# l6727a-5v.net
KiCad netlist of a schematic drawn in EAGLE
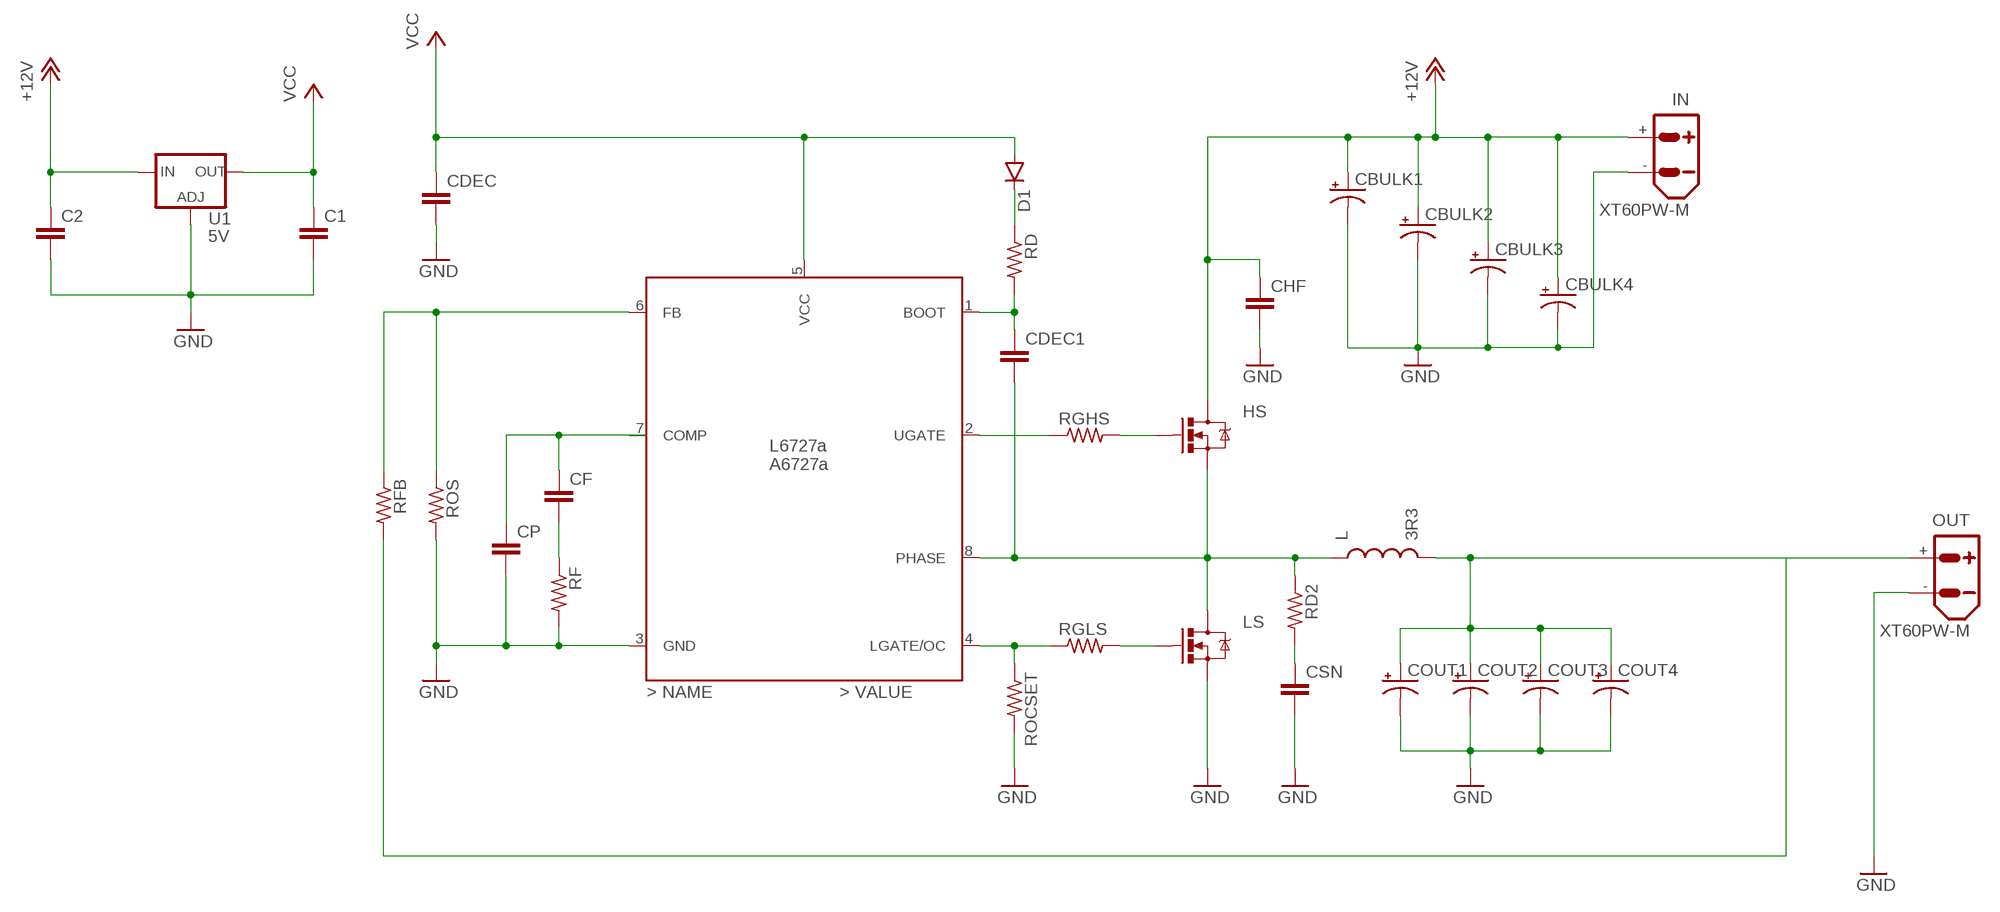
[diagram p0: schematic, sheet 1]

(export (version "E")
  (design (tool "Eeschema 10.0.6"))
  (components
    (comp (ref "C1")
      (value "C-EUC1206")
      (footprint "eagle-import:C1206")
      (libsource (lib "eagle-import") (part "C-EUC1206"))
    )
    (comp (ref "C2")
      (value "C-EUC1206")
      (footprint "eagle-import:C1206")
      (libsource (lib "eagle-import") (part "C-EUC1206"))
    )
    (comp (ref "CBULK1")
      (value "CPOL-USSANYO_SMD_E7")
      (footprint "eagle-import:SANYO-OSCON_SMD_E7")
      (libsource (lib "eagle-import") (part "CPOL-USSANYO_SMD_E7"))
    )
    (comp (ref "CBULK2")
      (value "CPOL-USSANYO_SMD_E7")
      (footprint "eagle-import:SANYO-OSCON_SMD_E7")
      (libsource (lib "eagle-import") (part "CPOL-USSANYO_SMD_E7"))
    )
    (comp (ref "CBULK3")
      (value "CPOL-USSANYO_SMD_E7")
      (footprint "eagle-import:SANYO-OSCON_SMD_E7")
      (libsource (lib "eagle-import") (part "CPOL-USSANYO_SMD_E7"))
    )
    (comp (ref "CBULK4")
      (value "CPOL-USSANYO_SMD_E7")
      (footprint "eagle-import:SANYO-OSCON_SMD_E7")
      (libsource (lib "eagle-import") (part "CPOL-USSANYO_SMD_E7"))
    )
    (comp (ref "CDEC")
      (value "C-EUC1206")
      (footprint "eagle-import:C1206")
      (libsource (lib "eagle-import") (part "C-EUC1206"))
    )
    (comp (ref "CDEC1")
      (value "C-EUC1206")
      (footprint "eagle-import:C1206")
      (libsource (lib "eagle-import") (part "C-EUC1206"))
    )
    (comp (ref "CF")
      (value "C-EUC1206")
      (footprint "eagle-import:C1206")
      (libsource (lib "eagle-import") (part "C-EUC1206"))
    )
    (comp (ref "CHF")
      (value "C-EUC1206")
      (footprint "eagle-import:C1206")
      (libsource (lib "eagle-import") (part "C-EUC1206"))
    )
    (comp (ref "COUT1")
      (value "CPOL-USSANYO_SMD_E7")
      (footprint "eagle-import:SANYO-OSCON_SMD_E7")
      (libsource (lib "eagle-import") (part "CPOL-USSANYO_SMD_E7"))
    )
    (comp (ref "COUT2")
      (value "CPOL-USSANYO_SMD_E7")
      (footprint "eagle-import:SANYO-OSCON_SMD_E7")
      (libsource (lib "eagle-import") (part "CPOL-USSANYO_SMD_E7"))
    )
    (comp (ref "COUT3")
      (value "CPOL-USSANYO_SMD_E7")
      (footprint "eagle-import:SANYO-OSCON_SMD_E7")
      (libsource (lib "eagle-import") (part "CPOL-USSANYO_SMD_E7"))
    )
    (comp (ref "COUT4")
      (value "CPOL-USSANYO_SMD_E7")
      (footprint "eagle-import:SANYO-OSCON_SMD_E7")
      (libsource (lib "eagle-import") (part "CPOL-USSANYO_SMD_E7"))
    )
    (comp (ref "CP")
      (value "C-EUC1206")
      (footprint "eagle-import:C1206")
      (libsource (lib "eagle-import") (part "C-EUC1206"))
    )
    (comp (ref "CSN")
      (value "C-EUC1206")
      (footprint "eagle-import:C1206")
      (libsource (lib "eagle-import") (part "C-EUC1206"))
    )
    (comp (ref "D1")
      (value "DIODESOD123")
      (footprint "eagle-import:SOD-123")
      (libsource (lib "eagle-import") (part "DIODESOD123"))
    )
    (comp (ref "HS")
      (value "MOSFET-NCHANNELFDS6630A")
      (footprint "eagle-import:SO08")
      (libsource (lib "eagle-import") (part "MOSFET-NCHANNELFDS6630A"))
    )
    (comp (ref "IC1")
      (value "L6727A")
      (footprint "eagle-import:SO-08")
      (libsource (lib "eagle-import") (part "L6727A"))
    )
    (comp (ref "IN")
      (value "XT60PW-M")
      (footprint "eagle-import:XT60PW-M")
      (libsource (lib "eagle-import") (part "XT60PW-M"))
    )
    (comp (ref "L")
      (value "3R3")
      (footprint "eagle-import:INDUCTOR_SDR1307")
      (libsource (lib "eagle-import") (part "INDUCTORSDR13-7-270ML"))
    )
    (comp (ref "LS")
      (value "MOSFET-NCHANNELFDS6630A")
      (footprint "eagle-import:SO08")
      (libsource (lib "eagle-import") (part "MOSFET-NCHANNELFDS6630A"))
    )
    (comp (ref "OUT")
      (value "XT60PW-M")
      (footprint "eagle-import:XT60PW-M")
      (libsource (lib "eagle-import") (part "XT60PW-M"))
    )
    (comp (ref "RD")
      (value "R-US_R0603")
      (footprint "eagle-import:R0603")
      (libsource (lib "eagle-import") (part "R-US_R0603"))
    )
    (comp (ref "RD2")
      (value "R-US_R0603")
      (footprint "eagle-import:R0603")
      (libsource (lib "eagle-import") (part "R-US_R0603"))
    )
    (comp (ref "RF")
      (value "R-US_R0603")
      (footprint "eagle-import:R0603")
      (libsource (lib "eagle-import") (part "R-US_R0603"))
    )
    (comp (ref "RFB")
      (value "R-US_R0603")
      (footprint "eagle-import:R0603")
      (libsource (lib "eagle-import") (part "R-US_R0603"))
    )
    (comp (ref "RGHS")
      (value "R-US_R0603")
      (footprint "eagle-import:R0603")
      (libsource (lib "eagle-import") (part "R-US_R0603"))
    )
    (comp (ref "RGLS")
      (value "R-US_R0603")
      (footprint "eagle-import:R0603")
      (libsource (lib "eagle-import") (part "R-US_R0603"))
    )
    (comp (ref "ROCSET")
      (value "R-US_R0603")
      (footprint "eagle-import:R0603")
      (libsource (lib "eagle-import") (part "R-US_R0603"))
    )
    (comp (ref "ROS")
      (value "R-US_R0603")
      (footprint "eagle-import:R0603")
      (libsource (lib "eagle-import") (part "R-US_R0603"))
    )
    (comp (ref "U1")
      (value "5V")
      (footprint "eagle-import:SOT223")
      (libsource (lib "eagle-import") (part "V_REG_317SMD"))
    )
  )
  (nets
    (net (code "1") (name "+12V") (class "Default")
      (node (ref "C2") (pin "1") (pinfunction "1_1") (pintype "passive"))
      (node (ref "CBULK1") (pin "+") (pinfunction "+_+") (pintype "passive"))
      (node (ref "CBULK2") (pin "+") (pinfunction "+_+") (pintype "passive"))
      (node (ref "CBULK3") (pin "+") (pinfunction "+_+") (pintype "passive"))
      (node (ref "CBULK4") (pin "+") (pinfunction "+_+") (pintype "passive"))
      (node (ref "CHF") (pin "1") (pinfunction "1_1") (pintype "passive"))
      (node (ref "HS") (pin "5") (pinfunction "D_5") (pintype "passive"))
      (node (ref "HS") (pin "6") (pinfunction "D_6") (pintype "passive"))
      (node (ref "HS") (pin "7") (pinfunction "D_7") (pintype "passive"))
      (node (ref "HS") (pin "8") (pinfunction "D_8") (pintype "passive"))
      (node (ref "IN") (pin "+") (pinfunction "+_+") (pintype "power_in"))
      (node (ref "U1") (pin "3") (pinfunction "IN_3") (pintype "input"))
    )
    (net (code "2") (name "GND") (class "Default")
      (node (ref "C1") (pin "2") (pinfunction "2_2") (pintype "passive"))
      (node (ref "C2") (pin "2") (pinfunction "2_2") (pintype "passive"))
      (node (ref "CBULK1") (pin "-") (pinfunction "-_-") (pintype "passive"))
      (node (ref "CBULK2") (pin "-") (pinfunction "-_-") (pintype "passive"))
      (node (ref "CBULK3") (pin "-") (pinfunction "-_-") (pintype "passive"))
      (node (ref "CBULK4") (pin "-") (pinfunction "-_-") (pintype "passive"))
      (node (ref "CDEC") (pin "2") (pinfunction "2_2") (pintype "passive"))
      (node (ref "CHF") (pin "2") (pinfunction "2_2") (pintype "passive"))
      (node (ref "COUT1") (pin "-") (pinfunction "-_-") (pintype "passive"))
      (node (ref "COUT2") (pin "-") (pinfunction "-_-") (pintype "passive"))
      (node (ref "COUT3") (pin "-") (pinfunction "-_-") (pintype "passive"))
      (node (ref "COUT4") (pin "-") (pinfunction "-_-") (pintype "passive"))
      (node (ref "CP") (pin "2") (pinfunction "2_2") (pintype "passive"))
      (node (ref "CSN") (pin "2") (pinfunction "2_2") (pintype "passive"))
      (node (ref "IC1") (pin "3") (pinfunction "GND_3") (pintype "power_in"))
      (node (ref "IN") (pin "-") (pinfunction "-_-") (pintype "power_in"))
      (node (ref "LS") (pin "1") (pinfunction "S_1") (pintype "passive"))
      (node (ref "LS") (pin "2") (pinfunction "S_2") (pintype "passive"))
      (node (ref "LS") (pin "3") (pinfunction "S_3") (pintype "passive"))
      (node (ref "OUT") (pin "-") (pinfunction "-_-") (pintype "power_in"))
      (node (ref "RF") (pin "2") (pinfunction "2_2") (pintype "passive"))
      (node (ref "ROCSET") (pin "2") (pinfunction "2_2") (pintype "passive"))
      (node (ref "ROS") (pin "2") (pinfunction "2_2") (pintype "passive"))
      (node (ref "U1") (pin "1") (pinfunction "ADJ_1") (pintype "input"))
    )
    (net (code "3") (name "Net-(CF-Pad1)") (class "Default")
      (node (ref "CF") (pin "1") (pinfunction "1_1") (pintype "passive"))
      (node (ref "CP") (pin "1") (pinfunction "1_1") (pintype "passive"))
    )
    (net (code "4") (name "Net-(CF-Pad2)") (class "Default")
      (node (ref "CF") (pin "2") (pinfunction "2_2") (pintype "passive"))
      (node (ref "RF") (pin "1") (pinfunction "1_1") (pintype "passive"))
    )
    (net (code "5") (name "Net-(CSN-Pad1)") (class "Default")
      (node (ref "CSN") (pin "1") (pinfunction "1_1") (pintype "passive"))
      (node (ref "RD2") (pin "2") (pinfunction "2_2") (pintype "passive"))
    )
    (net (code "6") (name "Net-(D1-PadC)") (class "Default")
      (node (ref "D1") (pin "C") (pinfunction "C_C") (pintype "passive"))
      (node (ref "RD") (pin "1") (pinfunction "1_1") (pintype "passive"))
    )
    (net (code "7") (name "Net-(HS-G)") (class "Default")
      (node (ref "HS") (pin "4") (pinfunction "G_4") (pintype "passive"))
      (node (ref "RGHS") (pin "2") (pinfunction "2_2") (pintype "passive"))
    )
    (net (code "8") (name "Net-(IC1-BOOT)") (class "Default")
      (node (ref "CDEC1") (pin "1") (pinfunction "1_1") (pintype "passive"))
      (node (ref "IC1") (pin "1") (pinfunction "BOOT_1") (pintype "power_in"))
      (node (ref "RD") (pin "2") (pinfunction "2_2") (pintype "passive"))
    )
    (net (code "9") (name "Net-(IC1-FB)") (class "Default")
      (node (ref "IC1") (pin "6") (pinfunction "FB_6") (pintype "input"))
      (node (ref "RFB") (pin "1") (pinfunction "1_1") (pintype "passive"))
      (node (ref "ROS") (pin "1") (pinfunction "1_1") (pintype "passive"))
    )
    (net (code "10") (name "Net-(IC1-LGATE{slash}OC)") (class "Default")
      (node (ref "IC1") (pin "4") (pinfunction "LGATE/OC_4") (pintype "output"))
      (node (ref "RGLS") (pin "1") (pinfunction "1_1") (pintype "passive"))
      (node (ref "ROCSET") (pin "1") (pinfunction "1_1") (pintype "passive"))
    )
    (net (code "11") (name "Net-(IC1-PHASE)") (class "Default")
      (node (ref "CDEC1") (pin "2") (pinfunction "2_2") (pintype "passive"))
      (node (ref "HS") (pin "1") (pinfunction "S_1") (pintype "passive"))
      (node (ref "HS") (pin "2") (pinfunction "S_2") (pintype "passive"))
      (node (ref "HS") (pin "3") (pinfunction "S_3") (pintype "passive"))
      (node (ref "IC1") (pin "8") (pinfunction "PHASE_8") (pintype "input"))
      (node (ref "L") (pin "P$1") (pinfunction "1_P$1") (pintype "passive"))
      (node (ref "LS") (pin "5") (pinfunction "D_5") (pintype "passive"))
      (node (ref "LS") (pin "6") (pinfunction "D_6") (pintype "passive"))
      (node (ref "LS") (pin "7") (pinfunction "D_7") (pintype "passive"))
      (node (ref "LS") (pin "8") (pinfunction "D_8") (pintype "passive"))
      (node (ref "RD2") (pin "1") (pinfunction "1_1") (pintype "passive"))
    )
    (net (code "12") (name "Net-(IC1-UGATE)") (class "Default")
      (node (ref "IC1") (pin "2") (pinfunction "UGATE_2") (pintype "output"))
      (node (ref "RGHS") (pin "1") (pinfunction "1_1") (pintype "passive"))
    )
    (net (code "13") (name "Net-(L-2)") (class "Default")
      (node (ref "COUT1") (pin "+") (pinfunction "+_+") (pintype "passive"))
      (node (ref "COUT2") (pin "+") (pinfunction "+_+") (pintype "passive"))
      (node (ref "COUT3") (pin "+") (pinfunction "+_+") (pintype "passive"))
      (node (ref "COUT4") (pin "+") (pinfunction "+_+") (pintype "passive"))
      (node (ref "L") (pin "P$2") (pinfunction "2_P$2") (pintype "passive"))
      (node (ref "OUT") (pin "+") (pinfunction "+_+") (pintype "power_in"))
      (node (ref "RFB") (pin "2") (pinfunction "2_2") (pintype "passive"))
    )
    (net (code "14") (name "Net-(LS-G)") (class "Default")
      (node (ref "LS") (pin "4") (pinfunction "G_4") (pintype "passive"))
      (node (ref "RGLS") (pin "2") (pinfunction "2_2") (pintype "passive"))
    )
    (net (code "15") (name "VCC") (class "Default")
      (node (ref "C1") (pin "1") (pinfunction "1_1") (pintype "passive"))
      (node (ref "CDEC") (pin "1") (pinfunction "1_1") (pintype "passive"))
      (node (ref "D1") (pin "A") (pinfunction "A_A") (pintype "passive"))
      (node (ref "IC1") (pin "5") (pinfunction "VCC_5") (pintype "power_in"))
      (node (ref "U1") (pin "2") (pinfunction "OUT_2") (pintype "output"))
    )
    (net (code "16") (name "unconnected-(IC1-COMP-Pad7)") (class "Default")
      (node (ref "IC1") (pin "7") (pinfunction "COMP_7") (pintype "input"))
    )
  )
)
